# H01R0_Frontend_1.net
KiCad netlist of a schematic drawn in Altium Designer
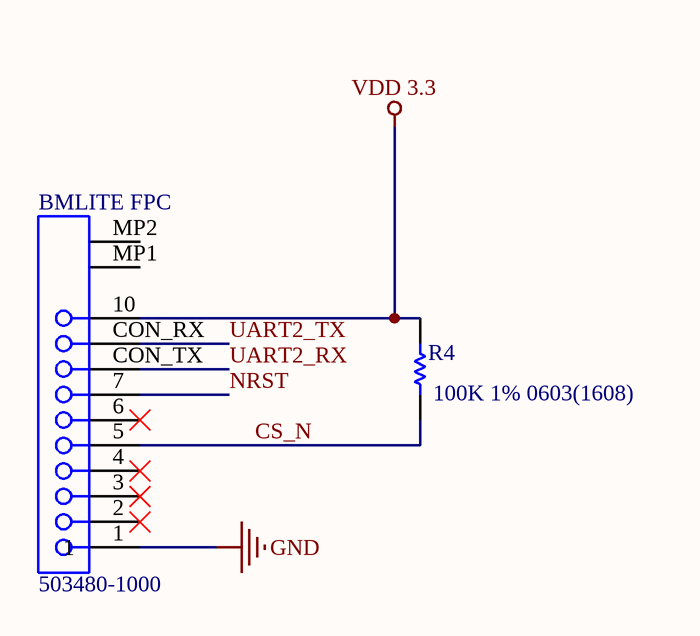
[diagram p0: H01R0_Frontend 1.SchDoc]

(export (version "E")
  (design (tool "Eeschema 10.0.6"))
  (components
    (comp (ref "BMLITE FPC")
      (value "503480-1000")
      (footprint "MOLX-503480-1000")
      (fields (field (name "MANUFACTURER") "Molex"))
      (libsource (lib "Altium Content Vault") (part "MOLX-503480-1000"))
    )
    (comp (ref "R4")
      (value "100K 1% 0603(1608)")
      (footprint "RESC0603(1608)_N")
      (description "100K 0.1W 1% 0603 (1608 Metric)  SMD")
      (fields (field (name "POWER") "0.1 W") (field (name "TOLERANCE") "1 %"))
      (libsource (lib "Altium Content Vault") (part "RES"))
    )
  )
  (nets
    (net (code "1") (name "/CS_N") (class "Default")
      (node (ref "BMLITE FPC") (pin "5") (pinfunction "5_5") (pintype "passive"))
      (node (ref "R4") (pin "1") (pinfunction "1_1") (pintype "passive"))
    )
    (net (code "2") (name "/NRST") (class "Default")
      (node (ref "BMLITE FPC") (pin "7") (pinfunction "7_7") (pintype "passive"))
    )
    (net (code "3") (name "/UART2_RX") (class "Default")
      (node (ref "BMLITE FPC") (pin "CON_TX") (pinfunction "8_CON_TX") (pintype "passive"))
    )
    (net (code "4") (name "/UART2_TX") (class "Default")
      (node (ref "BMLITE FPC") (pin "CON_RX") (pinfunction "CON_RX_CON_RX") (pintype "passive"))
    )
    (net (code "5") (name "GND") (class "Default")
      (node (ref "BMLITE FPC") (pin "1") (pinfunction "1_1") (pintype "passive"))
    )
    (net (code "6") (name "VDD 3.3") (class "Default")
      (node (ref "BMLITE FPC") (pin "10") (pinfunction "10_10") (pintype "passive"))
      (node (ref "R4") (pin "2") (pinfunction "2_2") (pintype "passive"))
    )
    (net (code "7") (name "unconnected-(BMLITE FPC-Pad2)") (class "Default")
      (node (ref "BMLITE FPC") (pin "2") (pinfunction "2_2") (pintype "passive+no_connect"))
    )
    (net (code "8") (name "unconnected-(BMLITE FPC-Pad3)") (class "Default")
      (node (ref "BMLITE FPC") (pin "3") (pinfunction "3_3") (pintype "passive+no_connect"))
    )
    (net (code "9") (name "unconnected-(BMLITE FPC-Pad4)") (class "Default")
      (node (ref "BMLITE FPC") (pin "4") (pinfunction "4_4") (pintype "passive+no_connect"))
    )
    (net (code "10") (name "unconnected-(BMLITE FPC-Pad6)") (class "Default")
      (node (ref "BMLITE FPC") (pin "6") (pinfunction "6_6") (pintype "passive+no_connect"))
    )
    (net (code "11") (name "unconnected-(BMLITE FPC-PadMP1)") (class "Default")
      (node (ref "BMLITE FPC") (pin "MP1") (pinfunction "MP1_MP1") (pintype "passive"))
    )
    (net (code "12") (name "unconnected-(BMLITE FPC-PadMP2)") (class "Default")
      (node (ref "BMLITE FPC") (pin "MP2") (pinfunction "MP2_MP2") (pintype "passive"))
    )
  )
)
